# transimp.net
KiCad netlist of a schematic drawn in EAGLE
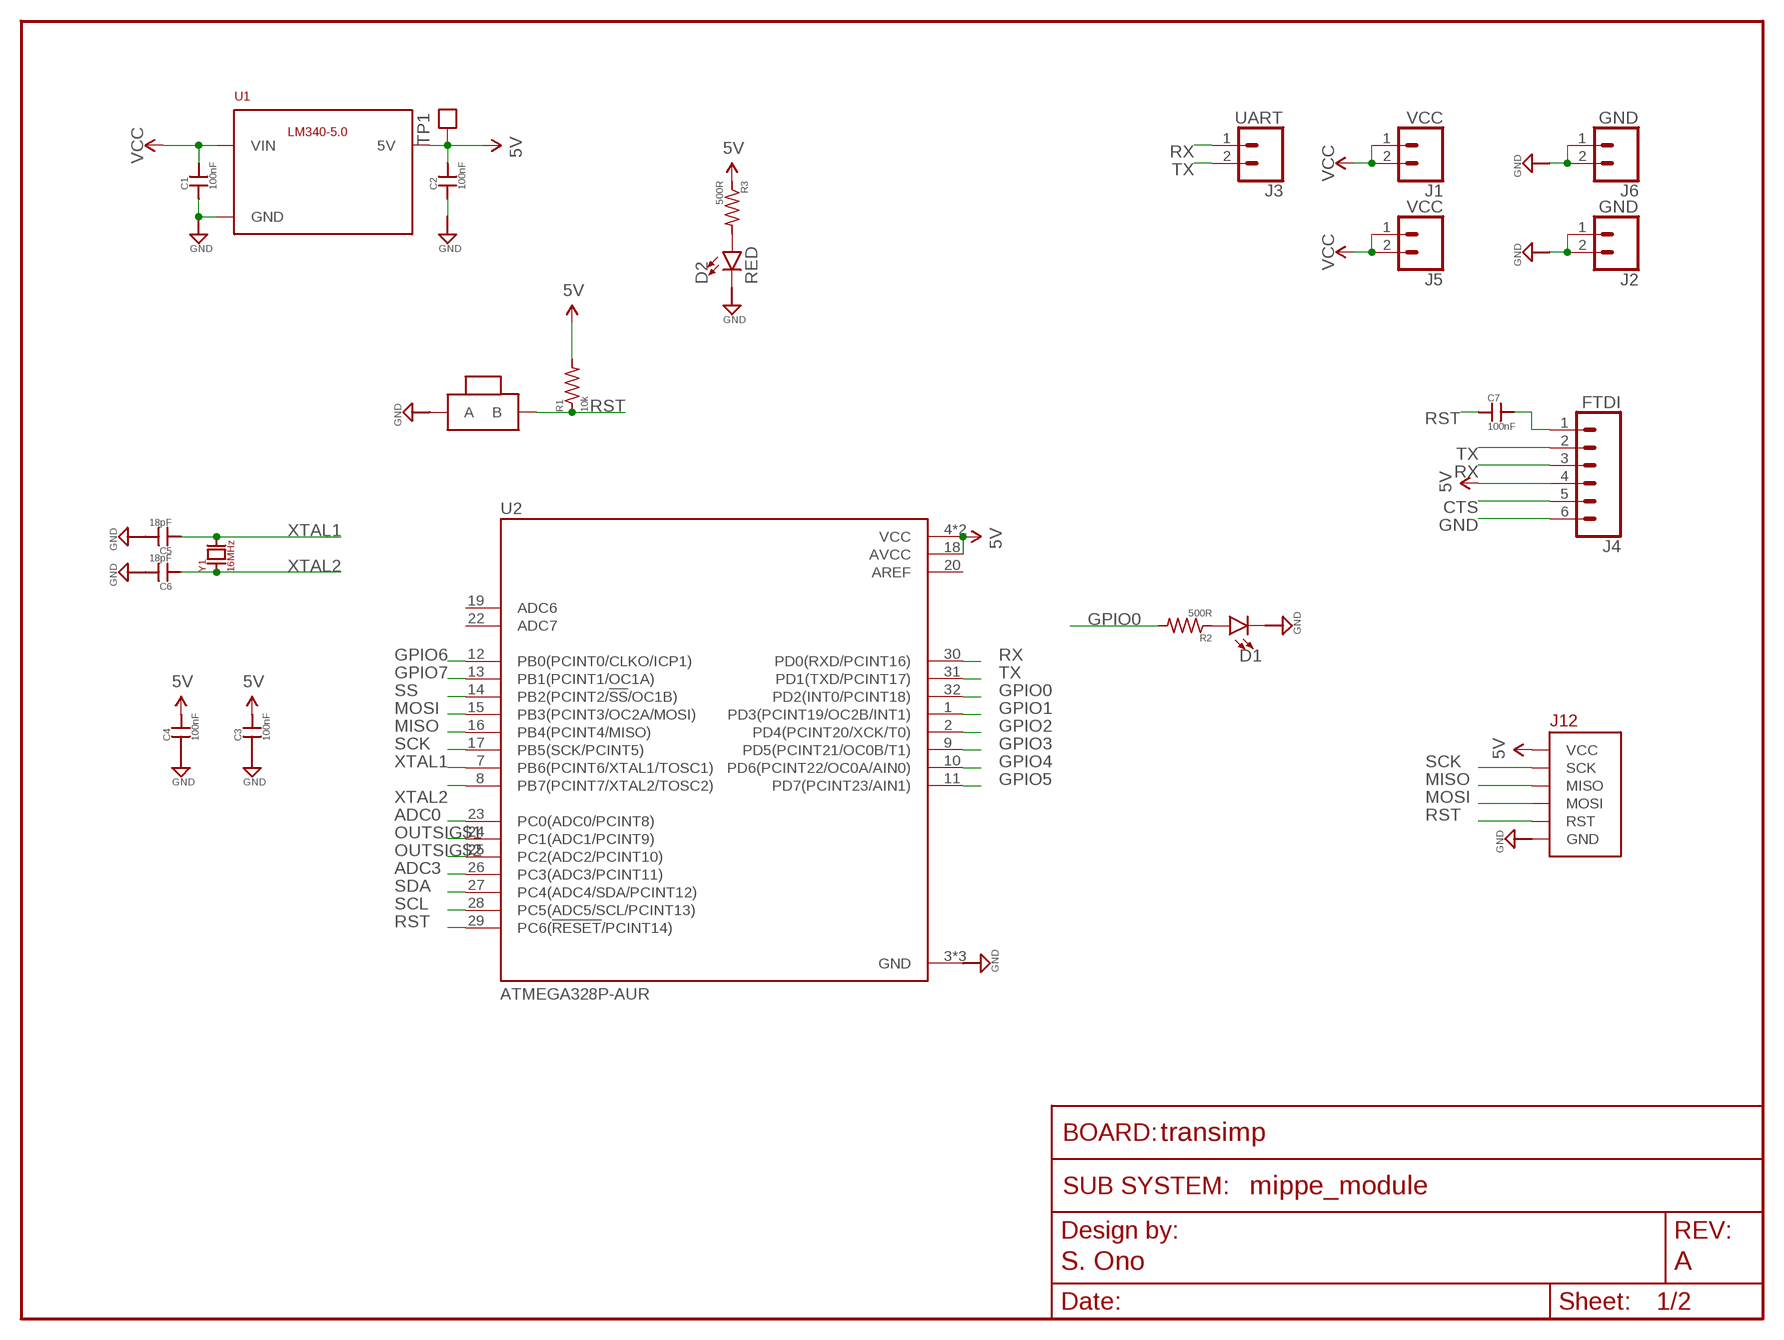
[diagram p0: schematic, sheet 1]
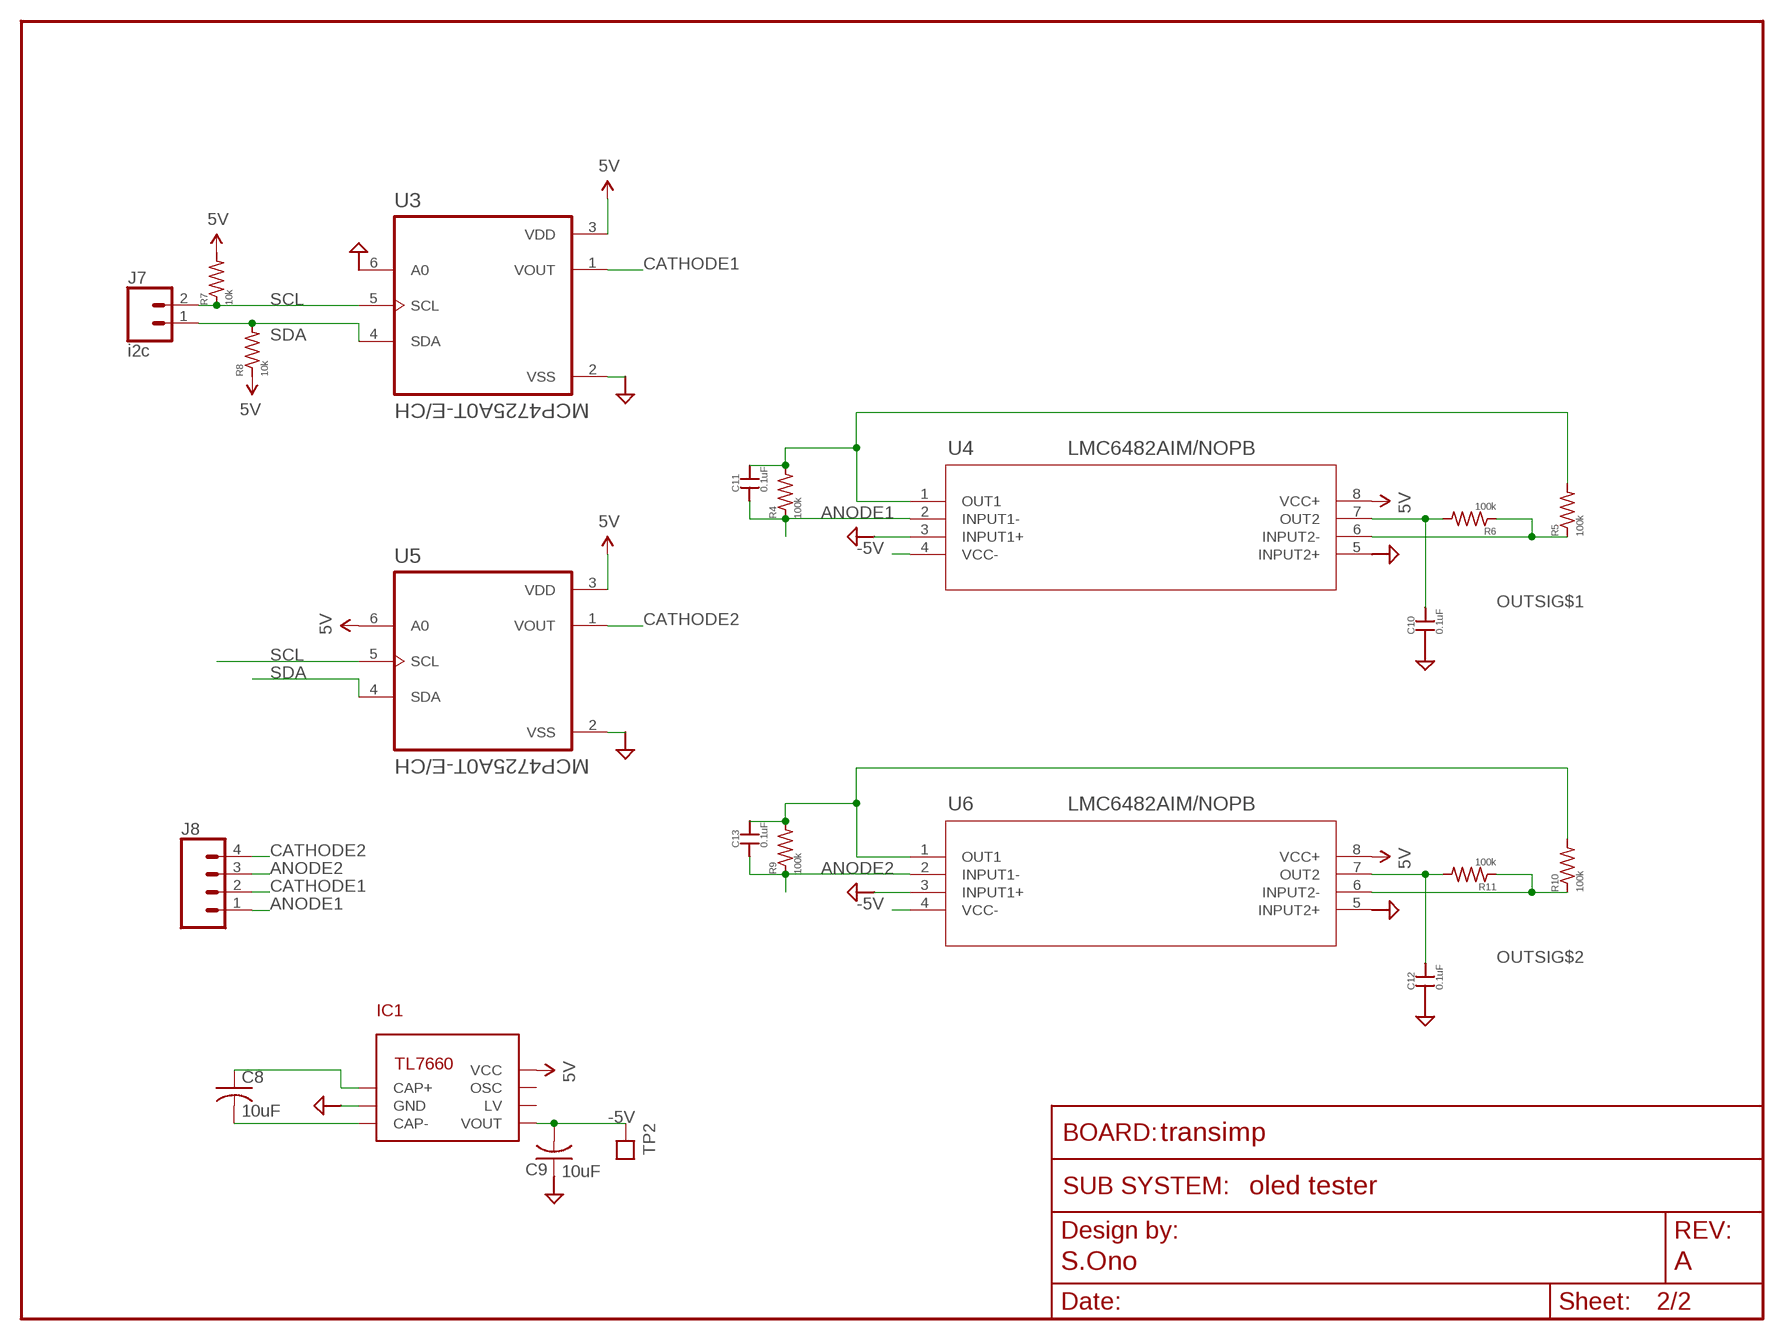
[diagram p1: schematic, sheet 2]

(export (version "E")
  (design (tool "Eeschema 10.0.6"))
  (components
    (comp (ref "C1")
      (value "100nF")
      (footprint "eagle-import:0402-CAP")
      (libsource (lib "eagle-import") (part "CAP0402-CAP"))
    )
    (comp (ref "C2")
      (value "100nF")
      (footprint "eagle-import:0402-CAP")
      (libsource (lib "eagle-import") (part "CAP0402-CAP"))
    )
    (comp (ref "C3")
      (value "100nF")
      (footprint "eagle-import:0402-CAP")
      (libsource (lib "eagle-import") (part "CAP0402-CAP"))
    )
    (comp (ref "C4")
      (value "100nF")
      (footprint "eagle-import:0402-CAP")
      (libsource (lib "eagle-import") (part "CAP0402-CAP"))
    )
    (comp (ref "C5")
      (value "18pF")
      (footprint "eagle-import:0402-CAP")
      (libsource (lib "eagle-import") (part "CAP0402-CAP"))
    )
    (comp (ref "C6")
      (value "18pF")
      (footprint "eagle-import:0402-CAP")
      (libsource (lib "eagle-import") (part "CAP0402-CAP"))
    )
    (comp (ref "C7")
      (value "100nF")
      (footprint "eagle-import:0402-CAP")
      (libsource (lib "eagle-import") (part "CAP0402-CAP"))
    )
    (comp (ref "D1")
      (value "LED0603")
      (footprint "eagle-import:LED-0603")
      (libsource (lib "eagle-import") (part "LED0603"))
    )
    (comp (ref "D2")
      (value "RED")
      (footprint "eagle-import:LED-0603")
      (libsource (lib "eagle-import") (part "LED0603"))
    )
    (comp (ref "J1")
      (value "VCC")
      (footprint "eagle-import:1X02")
      (libsource (lib "eagle-import") (part "CONN_02"))
    )
    (comp (ref "J2")
      (value "GND")
      (footprint "eagle-import:1X02")
      (libsource (lib "eagle-import") (part "CONN_02"))
    )
    (comp (ref "J3")
      (value "UART")
      (footprint "eagle-import:1X02")
      (libsource (lib "eagle-import") (part "CONN_02"))
    )
    (comp (ref "J4")
      (value "FTDI")
      (footprint "eagle-import:1X06_NO_SILK")
      (libsource (lib "eagle-import") (part "CONN_06NO_SILK_FEMALE_PTH"))
    )
    (comp (ref "J5")
      (value "VCC")
      (footprint "eagle-import:1X02")
      (libsource (lib "eagle-import") (part "CONN_02"))
    )
    (comp (ref "J6")
      (value "GND")
      (footprint "eagle-import:1X02")
      (libsource (lib "eagle-import") (part "CONN_02"))
    )
    (comp (ref "J12")
      (value "BURNIN")
      (footprint "eagle-import:BURNIN")
      (libsource (lib "eagle-import") (part "BURNIN"))
    )
    (comp (ref "R1")
      (value "10k")
      (footprint "eagle-import:R0402")
      (libsource (lib "eagle-import") (part "R-US_R0402"))
    )
    (comp (ref "R2")
      (value "500R")
      (footprint "eagle-import:R0402")
      (libsource (lib "eagle-import") (part "R-US_R0402"))
    )
    (comp (ref "R3")
      (value "500R")
      (footprint "eagle-import:R0402")
      (libsource (lib "eagle-import") (part "R-US_R0402"))
    )
    (comp (ref "SW1")
      (value "BTN-PTS810")
      (footprint "eagle-import:BTN_PTS810")
      (libsource (lib "eagle-import") (part "BTN-PTS810"))
    )
    (comp (ref "TP1")
      (value "TEST_POINTTHRU")
      (footprint "eagle-import:TEST_POINT")
      (libsource (lib "eagle-import") (part "TEST_POINTTHRU"))
    )
    (comp (ref "U1")
      (value "LM340MPX-5.0230")
      (footprint "eagle-import:SOT230P700X180-4N")
      (libsource (lib "eagle-import") (part "LM340MPX-5.0230"))
    )
    (comp (ref "U2")
      (value "ATMEGA328P-AUR")
      (footprint "eagle-import:QFP80P900X900X120-32N")
      (fields (field (name "DIGI-KEY_PART_NUMBER") "ATMEGA328P-AURCT-ND") (field (name "MF") "Microchip"))
      (libsource (lib "eagle-import") (part "ATMEGA328P-AUR"))
    )
    (comp (ref "Y1")
      (value "16MHz")
      (footprint "eagle-import:XTAL500X320X130N")
      (libsource (lib "eagle-import") (part "CRYSTAL_SMOL"))
    )
    (comp (ref "C8")
      (value "10uF")
      (footprint "eagle-import:CAP_3MM")
      (libsource (lib "eagle-import") (part "CAP_ELEC_3MM_SMD"))
    )
    (comp (ref "C9")
      (value "10uF")
      (footprint "eagle-import:CAP_3MM")
      (libsource (lib "eagle-import") (part "CAP_ELEC_3MM_SMD"))
    )
    (comp (ref "C10")
      (value "0.1uF")
      (footprint "eagle-import:0402-CAP")
      (libsource (lib "eagle-import") (part "CAP0402-CAP"))
    )
    (comp (ref "C11")
      (value "0.1uF")
      (footprint "eagle-import:0402-CAP")
      (libsource (lib "eagle-import") (part "CAP0402-CAP"))
    )
    (comp (ref "C12")
      (value "0.1uF")
      (footprint "eagle-import:0402-CAP")
      (libsource (lib "eagle-import") (part "CAP0402-CAP"))
    )
    (comp (ref "C13")
      (value "0.1uF")
      (footprint "eagle-import:0402-CAP")
      (libsource (lib "eagle-import") (part "CAP0402-CAP"))
    )
    (comp (ref "IC1")
      (value "TL7660")
      (footprint "eagle-import:8SOICW")
      (libsource (lib "eagle-import") (part "TL7660"))
    )
    (comp (ref "J7")
      (value "i2c")
      (footprint "eagle-import:1X02")
      (libsource (lib "eagle-import") (part "CONN_02"))
    )
    (comp (ref "J8")
      (value "CONN_04")
      (footprint "eagle-import:1X04")
      (libsource (lib "eagle-import") (part "CONN_04"))
    )
    (comp (ref "R4")
      (value "100k")
      (footprint "eagle-import:R0402")
      (libsource (lib "eagle-import") (part "R-US_R0402"))
    )
    (comp (ref "R5")
      (value "100k")
      (footprint "eagle-import:R0402")
      (libsource (lib "eagle-import") (part "R-US_R0402"))
    )
    (comp (ref "R6")
      (value "100k")
      (footprint "eagle-import:R0402")
      (libsource (lib "eagle-import") (part "R-US_R0402"))
    )
    (comp (ref "R7")
      (value "10k")
      (footprint "eagle-import:R0402")
      (libsource (lib "eagle-import") (part "R-US_R0402"))
    )
    (comp (ref "R8")
      (value "10k")
      (footprint "eagle-import:R0402")
      (libsource (lib "eagle-import") (part "R-US_R0402"))
    )
    (comp (ref "R9")
      (value "100k")
      (footprint "eagle-import:R0402")
      (libsource (lib "eagle-import") (part "R-US_R0402"))
    )
    (comp (ref "R10")
      (value "100k")
      (footprint "eagle-import:R0402")
      (libsource (lib "eagle-import") (part "R-US_R0402"))
    )
    (comp (ref "R11")
      (value "100k")
      (footprint "eagle-import:R0402")
      (libsource (lib "eagle-import") (part "R-US_R0402"))
    )
    (comp (ref "TP2")
      (value "TEST_POINTTHRU")
      (footprint "eagle-import:TEST_POINT")
      (libsource (lib "eagle-import") (part "TEST_POINTTHRU"))
    )
    (comp (ref "U3")
      (value "MCP4725A0T-E/CH")
      (footprint "eagle-import:SOT95P270X145-6N")
      (fields (field (name "DIGI-KEY_PART_NUMBER") "MCP4725A0T-E/CHCT-ND") (field (name "MF") "Microchip"))
      (libsource (lib "eagle-import") (part "MCP4725A0T-E/CH"))
    )
    (comp (ref "U4")
      (value "LMC6482AIM/NOPB")
      (footprint "eagle-import:M08A")
      (libsource (lib "eagle-import") (part "LMC6482AIM/NOPB"))
    )
    (comp (ref "U5")
      (value "MCP4725A0T-E/CH")
      (footprint "eagle-import:SOT95P270X145-6N")
      (fields (field (name "DIGI-KEY_PART_NUMBER") "MCP4725A0T-E/CHCT-ND") (field (name "MF") "Microchip"))
      (libsource (lib "eagle-import") (part "MCP4725A0T-E/CH"))
    )
    (comp (ref "U6")
      (value "LMC6482AIM/NOPB")
      (footprint "eagle-import:M08A")
      (libsource (lib "eagle-import") (part "LMC6482AIM/NOPB"))
    )
  )
  (nets
    (net (code "1") (name "-5V") (class "Default")
      (node (ref "C9") (pin "NEG") (pinfunction "NEG_NEG") (pintype "passive"))
      (node (ref "IC1") (pin "5") (pinfunction "VOUT_5") (pintype "bidirectional"))
      (node (ref "TP2") (pin "1") (pinfunction "P$1_1") (pintype "bidirectional"))
      (node (ref "U4") (pin "4") (pinfunction "VCC-_4") (pintype "passive"))
      (node (ref "U6") (pin "4") (pinfunction "VCC-_4") (pintype "passive"))
    )
    (net (code "2") (name "5V") (class "Default")
      (node (ref "C2") (pin "2") (pinfunction "2_2") (pintype "passive"))
      (node (ref "C3") (pin "2") (pinfunction "2_2") (pintype "passive"))
      (node (ref "C4") (pin "2") (pinfunction "2_2") (pintype "passive"))
      (node (ref "IC1") (pin "8") (pinfunction "VCC_8") (pintype "bidirectional"))
      (node (ref "J12") (pin "3.3V") (pinfunction "VCC_3.3V") (pintype "power_in"))
      (node (ref "J4") (pin "4") (pinfunction "4_4") (pintype "passive"))
      (node (ref "R1") (pin "2") (pinfunction "2_2") (pintype "passive"))
      (node (ref "R3") (pin "1") (pinfunction "1_1") (pintype "passive"))
      (node (ref "R7") (pin "2") (pinfunction "2_2") (pintype "passive"))
      (node (ref "R8") (pin "1") (pinfunction "1_1") (pintype "passive"))
      (node (ref "TP1") (pin "1") (pinfunction "P$1_1") (pintype "bidirectional"))
      (node (ref "U1") (pin "3") (pinfunction "5V_3") (pintype "power_in"))
      (node (ref "U2") (pin "18") (pinfunction "AVCC_18") (pintype "power_in"))
      (node (ref "U2") (pin "4") (pinfunction "VCC_4") (pintype "power_in"))
      (node (ref "U2") (pin "6") (pinfunction "VCC_6") (pintype "power_in"))
      (node (ref "U3") (pin "3") (pinfunction "VDD_3") (pintype "power_in"))
      (node (ref "U4") (pin "8") (pinfunction "VCC+_8") (pintype "passive"))
      (node (ref "U5") (pin "3") (pinfunction "VDD_3") (pintype "power_in"))
      (node (ref "U5") (pin "6") (pinfunction "A0_6") (pintype "input"))
      (node (ref "U6") (pin "8") (pinfunction "VCC+_8") (pintype "passive"))
    )
    (net (code "3") (name "ADC0") (class "Default")
      (node (ref "U2") (pin "23") (pinfunction "PC0(ADC0/PCINT8)_23") (pintype "bidirectional"))
    )
    (net (code "4") (name "ADC3") (class "Default")
      (node (ref "U2") (pin "26") (pinfunction "PC3(ADC3/PCINT11)_26") (pintype "bidirectional"))
    )
    (net (code "5") (name "ANODE1") (class "Default")
      (node (ref "C11") (pin "1") (pinfunction "1_1") (pintype "passive"))
      (node (ref "J8") (pin "1") (pinfunction "1_1") (pintype "passive"))
      (node (ref "R4") (pin "1") (pinfunction "1_1") (pintype "passive"))
      (node (ref "U4") (pin "2") (pinfunction "INPUT1-_2") (pintype "passive"))
    )
    (net (code "6") (name "ANODE2") (class "Default")
      (node (ref "C13") (pin "1") (pinfunction "1_1") (pintype "passive"))
      (node (ref "J8") (pin "3") (pinfunction "3_3") (pintype "passive"))
      (node (ref "R9") (pin "1") (pinfunction "1_1") (pintype "passive"))
      (node (ref "U6") (pin "2") (pinfunction "INPUT1-_2") (pintype "passive"))
    )
    (net (code "7") (name "AREF") (class "Default")
      (node (ref "U2") (pin "20") (pinfunction "AREF_20") (pintype "power_in"))
    )
    (net (code "8") (name "CATHODE1") (class "Default")
      (node (ref "J8") (pin "2") (pinfunction "2_2") (pintype "passive"))
      (node (ref "U3") (pin "1") (pinfunction "VOUT_1") (pintype "output"))
    )
    (net (code "9") (name "CATHODE2") (class "Default")
      (node (ref "J8") (pin "4") (pinfunction "4_4") (pintype "passive"))
      (node (ref "U5") (pin "1") (pinfunction "VOUT_1") (pintype "output"))
    )
    (net (code "10") (name "CTS") (class "Default")
      (node (ref "J4") (pin "5") (pinfunction "5_5") (pintype "passive"))
    )
    (net (code "11") (name "GND") (class "Default")
      (node (ref "C1") (pin "1") (pinfunction "1_1") (pintype "passive"))
      (node (ref "C10") (pin "1") (pinfunction "1_1") (pintype "passive"))
      (node (ref "C12") (pin "1") (pinfunction "1_1") (pintype "passive"))
      (node (ref "C2") (pin "1") (pinfunction "1_1") (pintype "passive"))
      (node (ref "C3") (pin "1") (pinfunction "1_1") (pintype "passive"))
      (node (ref "C4") (pin "1") (pinfunction "1_1") (pintype "passive"))
      (node (ref "C5") (pin "2") (pinfunction "2_2") (pintype "passive"))
      (node (ref "C6") (pin "2") (pinfunction "2_2") (pintype "passive"))
      (node (ref "C9") (pin "POS") (pinfunction "POS_POS") (pintype "passive"))
      (node (ref "D1") (pin "C") (pinfunction "C_C") (pintype "passive"))
      (node (ref "D2") (pin "C") (pinfunction "C_C") (pintype "passive"))
      (node (ref "IC1") (pin "3") (pinfunction "GND_3") (pintype "bidirectional"))
      (node (ref "J12") (pin "GND") (pinfunction "GND_GND") (pintype "power_in"))
      (node (ref "J2") (pin "1") (pinfunction "1_1") (pintype "passive"))
      (node (ref "J2") (pin "2") (pinfunction "2_2") (pintype "passive"))
      (node (ref "J4") (pin "6") (pinfunction "6_6") (pintype "passive"))
      (node (ref "J6") (pin "1") (pinfunction "1_1") (pintype "passive"))
      (node (ref "J6") (pin "2") (pinfunction "2_2") (pintype "passive"))
      (node (ref "SW1") (pin "1") (pinfunction "A_1") (pintype "bidirectional"))
      (node (ref "SW1") (pin "2") (pinfunction "A_2") (pintype "bidirectional"))
      (node (ref "U1") (pin "2") (pinfunction "GND_2") (pintype "power_in"))
      (node (ref "U1") (pin "4") (pinfunction "GND_4") (pintype "power_in"))
      (node (ref "U2") (pin "21") (pinfunction "GND_21") (pintype "power_in"))
      (node (ref "U2") (pin "3") (pinfunction "GND_3") (pintype "power_in"))
      (node (ref "U2") (pin "5") (pinfunction "GND_5") (pintype "power_in"))
      (node (ref "U3") (pin "2") (pinfunction "VSS_2") (pintype "power_in"))
      (node (ref "U3") (pin "6") (pinfunction "A0_6") (pintype "input"))
      (node (ref "U4") (pin "3") (pinfunction "INPUT1+_3") (pintype "passive"))
      (node (ref "U4") (pin "5") (pinfunction "INPUT2+_5") (pintype "passive"))
      (node (ref "U5") (pin "2") (pinfunction "VSS_2") (pintype "power_in"))
      (node (ref "U6") (pin "3") (pinfunction "INPUT1+_3") (pintype "passive"))
      (node (ref "U6") (pin "5") (pinfunction "INPUT2+_5") (pintype "passive"))
    )
    (net (code "12") (name "GPIO0") (class "Default")
      (node (ref "R2") (pin "2") (pinfunction "2_2") (pintype "passive"))
      (node (ref "U2") (pin "32") (pinfunction "PD2(INT0/PCINT18)_32") (pintype "bidirectional"))
    )
    (net (code "13") (name "GPIO1") (class "Default")
      (node (ref "U2") (pin "1") (pinfunction "PD3(PCINT19/OC2B/INT1)_1") (pintype "bidirectional"))
    )
    (net (code "14") (name "GPIO2") (class "Default")
      (node (ref "U2") (pin "2") (pinfunction "PD4(PCINT20/XCK/T0)_2") (pintype "bidirectional"))
    )
    (net (code "15") (name "GPIO3") (class "Default")
      (node (ref "U2") (pin "9") (pinfunction "PD5(PCINT21/OC0B/T1)_9") (pintype "bidirectional"))
    )
    (net (code "16") (name "GPIO4") (class "Default")
      (node (ref "U2") (pin "10") (pinfunction "PD6(PCINT22/OC0A/AIN0)_10") (pintype "bidirectional"))
    )
    (net (code "17") (name "GPIO5") (class "Default")
      (node (ref "U2") (pin "11") (pinfunction "PD7(PCINT23/AIN1)_11") (pintype "bidirectional"))
    )
    (net (code "18") (name "GPIO6") (class "Default")
      (node (ref "U2") (pin "12") (pinfunction "PB0(PCINT0/CLKO/ICP1)_12") (pintype "bidirectional"))
    )
    (net (code "19") (name "GPIO7") (class "Default")
      (node (ref "U2") (pin "13") (pinfunction "PB1(PCINT1/OC1A)_13") (pintype "bidirectional"))
    )
    (net (code "20") (name "MISO") (class "Default")
      (node (ref "J12") (pin "MISO") (pinfunction "MISO_MISO") (pintype "bidirectional"))
      (node (ref "U2") (pin "16") (pinfunction "PB4(PCINT4/MISO)_16") (pintype "bidirectional"))
    )
    (net (code "21") (name "MOSI") (class "Default")
      (node (ref "J12") (pin "MOSI") (pinfunction "MOSI_MOSI") (pintype "bidirectional"))
      (node (ref "U2") (pin "15") (pinfunction "PB3(PCINT3/OC2A/MOSI)_15") (pintype "bidirectional"))
    )
    (net (code "22") (name "Net-(C7-Pad2)") (class "Default")
      (node (ref "C7") (pin "2") (pinfunction "2_2") (pintype "passive"))
      (node (ref "J4") (pin "1") (pinfunction "1_1") (pintype "passive"))
    )
    (net (code "23") (name "Net-(D1-PadA)") (class "Default")
      (node (ref "D1") (pin "A") (pinfunction "A_A") (pintype "passive"))
      (node (ref "R2") (pin "1") (pinfunction "1_1") (pintype "passive"))
    )
    (net (code "24") (name "Net-(D2-PadA)") (class "Default")
      (node (ref "D2") (pin "A") (pinfunction "A_A") (pintype "passive"))
      (node (ref "R3") (pin "2") (pinfunction "2_2") (pintype "passive"))
    )
    (net (code "25") (name "Net-(IC1-CAP+)") (class "Default")
      (node (ref "C8") (pin "POS") (pinfunction "POS_POS") (pintype "passive"))
      (node (ref "IC1") (pin "2") (pinfunction "CAP+_2") (pintype "bidirectional"))
    )
    (net (code "26") (name "Net-(IC1-CAP-)") (class "Default")
      (node (ref "C8") (pin "NEG") (pinfunction "NEG_NEG") (pintype "passive"))
      (node (ref "IC1") (pin "4") (pinfunction "CAP-_4") (pintype "bidirectional"))
    )
    (net (code "27") (name "Net-(U4-INPUT2-)") (class "Default")
      (node (ref "R5") (pin "1") (pinfunction "1_1") (pintype "passive"))
      (node (ref "R6") (pin "1") (pinfunction "1_1") (pintype "passive"))
      (node (ref "U4") (pin "6") (pinfunction "INPUT2-_6") (pintype "passive"))
    )
    (net (code "28") (name "Net-(U4-OUT1)") (class "Default")
      (node (ref "C11") (pin "2") (pinfunction "2_2") (pintype "passive"))
      (node (ref "R4") (pin "2") (pinfunction "2_2") (pintype "passive"))
      (node (ref "R5") (pin "2") (pinfunction "2_2") (pintype "passive"))
      (node (ref "U4") (pin "1") (pinfunction "OUT1_1") (pintype "passive"))
    )
    (net (code "29") (name "Net-(U6-INPUT2-)") (class "Default")
      (node (ref "R10") (pin "1") (pinfunction "1_1") (pintype "passive"))
      (node (ref "R11") (pin "1") (pinfunction "1_1") (pintype "passive"))
      (node (ref "U6") (pin "6") (pinfunction "INPUT2-_6") (pintype "passive"))
    )
    (net (code "30") (name "Net-(U6-OUT1)") (class "Default")
      (node (ref "C13") (pin "2") (pinfunction "2_2") (pintype "passive"))
      (node (ref "R10") (pin "2") (pinfunction "2_2") (pintype "passive"))
      (node (ref "R9") (pin "2") (pinfunction "2_2") (pintype "passive"))
      (node (ref "U6") (pin "1") (pinfunction "OUT1_1") (pintype "passive"))
    )
    (net (code "31") (name "OUTSIG$1") (class "Default")
      (node (ref "C10") (pin "2") (pinfunction "2_2") (pintype "passive"))
      (node (ref "R6") (pin "2") (pinfunction "2_2") (pintype "passive"))
      (node (ref "U2") (pin "24") (pinfunction "PC1(ADC1/PCINT9)_24") (pintype "bidirectional"))
      (node (ref "U4") (pin "7") (pinfunction "OUT2_7") (pintype "passive"))
    )
    (net (code "32") (name "OUTSIG$2") (class "Default")
      (node (ref "C12") (pin "2") (pinfunction "2_2") (pintype "passive"))
      (node (ref "R11") (pin "2") (pinfunction "2_2") (pintype "passive"))
      (node (ref "U2") (pin "25") (pinfunction "PC2(ADC2/PCINT10)_25") (pintype "bidirectional"))
      (node (ref "U6") (pin "7") (pinfunction "OUT2_7") (pintype "passive"))
    )
    (net (code "33") (name "RST") (class "Default")
      (node (ref "C7") (pin "1") (pinfunction "1_1") (pintype "passive"))
      (node (ref "J12") (pin "RST") (pinfunction "RST_RST") (pintype "bidirectional"))
      (node (ref "R1") (pin "1") (pinfunction "1_1") (pintype "passive"))
      (node (ref "SW1") (pin "3") (pinfunction "B_3") (pintype "bidirectional"))
      (node (ref "SW1") (pin "4") (pinfunction "B_4") (pintype "bidirectional"))
      (node (ref "U2") (pin "29") (pinfunction "PC6(~{RESET}/PCINT14)_29") (pintype "bidirectional"))
    )
    (net (code "34") (name "RX") (class "Default")
      (node (ref "J3") (pin "1") (pinfunction "1_1") (pintype "passive"))
      (node (ref "J4") (pin "3") (pinfunction "3_3") (pintype "passive"))
      (node (ref "U2") (pin "30") (pinfunction "PD0(RXD/PCINT16)_30") (pintype "bidirectional"))
    )
    (net (code "35") (name "SCK") (class "Default")
      (node (ref "J12") (pin "SCK") (pinfunction "SCK_SCK") (pintype "bidirectional"))
      (node (ref "U2") (pin "17") (pinfunction "PB5(SCK/PCINT5)_17") (pintype "bidirectional"))
    )
    (net (code "36") (name "SCL") (class "Default")
      (node (ref "J7") (pin "2") (pinfunction "2_2") (pintype "passive"))
      (node (ref "R7") (pin "1") (pinfunction "1_1") (pintype "passive"))
      (node (ref "U2") (pin "28") (pinfunction "PC5(ADC5/SCL/PCINT13)_28") (pintype "bidirectional"))
      (node (ref "U3") (pin "5") (pinfunction "SCL_5") (pintype "input"))
      (node (ref "U5") (pin "5") (pinfunction "SCL_5") (pintype "input"))
    )
    (net (code "37") (name "SDA") (class "Default")
      (node (ref "J7") (pin "1") (pinfunction "1_1") (pintype "passive"))
      (node (ref "R8") (pin "2") (pinfunction "2_2") (pintype "passive"))
      (node (ref "U2") (pin "27") (pinfunction "PC4(ADC4/SDA/PCINT12)_27") (pintype "bidirectional"))
      (node (ref "U3") (pin "4") (pinfunction "SDA_4") (pintype "bidirectional"))
      (node (ref "U5") (pin "4") (pinfunction "SDA_4") (pintype "bidirectional"))
    )
    (net (code "38") (name "SS") (class "Default")
      (node (ref "U2") (pin "14") (pinfunction "PB2(PCINT2/~{SS}/OC1B)_14") (pintype "bidirectional"))
    )
    (net (code "39") (name "TX") (class "Default")
      (node (ref "J3") (pin "2") (pinfunction "2_2") (pintype "passive"))
      (node (ref "J4") (pin "2") (pinfunction "2_2") (pintype "passive"))
      (node (ref "U2") (pin "31") (pinfunction "PD1(TXD/PCINT17)_31") (pintype "bidirectional"))
    )
    (net (code "40") (name "VCC") (class "Default")
      (node (ref "C1") (pin "2") (pinfunction "2_2") (pintype "passive"))
      (node (ref "J1") (pin "1") (pinfunction "1_1") (pintype "passive"))
      (node (ref "J1") (pin "2") (pinfunction "2_2") (pintype "passive"))
      (node (ref "J5") (pin "1") (pinfunction "1_1") (pintype "passive"))
      (node (ref "J5") (pin "2") (pinfunction "2_2") (pintype "passive"))
      (node (ref "U1") (pin "1") (pinfunction "VIN_1") (pintype "power_in"))
    )
    (net (code "41") (name "XTAL1") (class "Default")
      (node (ref "C5") (pin "1") (pinfunction "1_1") (pintype "passive"))
      (node (ref "U2") (pin "7") (pinfunction "PB6(PCINT6/XTAL1/TOSC1)_7") (pintype "bidirectional"))
      (node (ref "Y1") (pin "2") (pinfunction "B_2") (pintype "passive"))
    )
    (net (code "42") (name "XTAL2") (class "Default")
      (node (ref "C6") (pin "1") (pinfunction "1_1") (pintype "passive"))
      (node (ref "U2") (pin "8") (pinfunction "PB7(PCINT7/XTAL2/TOSC2)_8") (pintype "bidirectional"))
      (node (ref "Y1") (pin "1") (pinfunction "A_1") (pintype "passive"))
    )
    (net (code "43") (name "unconnected-(IC1-LV-Pad6)") (class "Default")
      (node (ref "IC1") (pin "6") (pinfunction "LV_6") (pintype "bidirectional"))
    )
    (net (code "44") (name "unconnected-(IC1-OSC-Pad7)") (class "Default")
      (node (ref "IC1") (pin "7") (pinfunction "OSC_7") (pintype "bidirectional"))
    )
    (net (code "45") (name "unconnected-(U2-ADC6-Pad19)") (class "Default")
      (node (ref "U2") (pin "19") (pinfunction "ADC6_19") (pintype "input"))
    )
    (net (code "46") (name "unconnected-(U2-ADC7-Pad22)") (class "Default")
      (node (ref "U2") (pin "22") (pinfunction "ADC7_22") (pintype "input"))
    )
  )
)
